# 1ch_motor_drive.net
KiCad netlist of a schematic drawn in Altium Designer
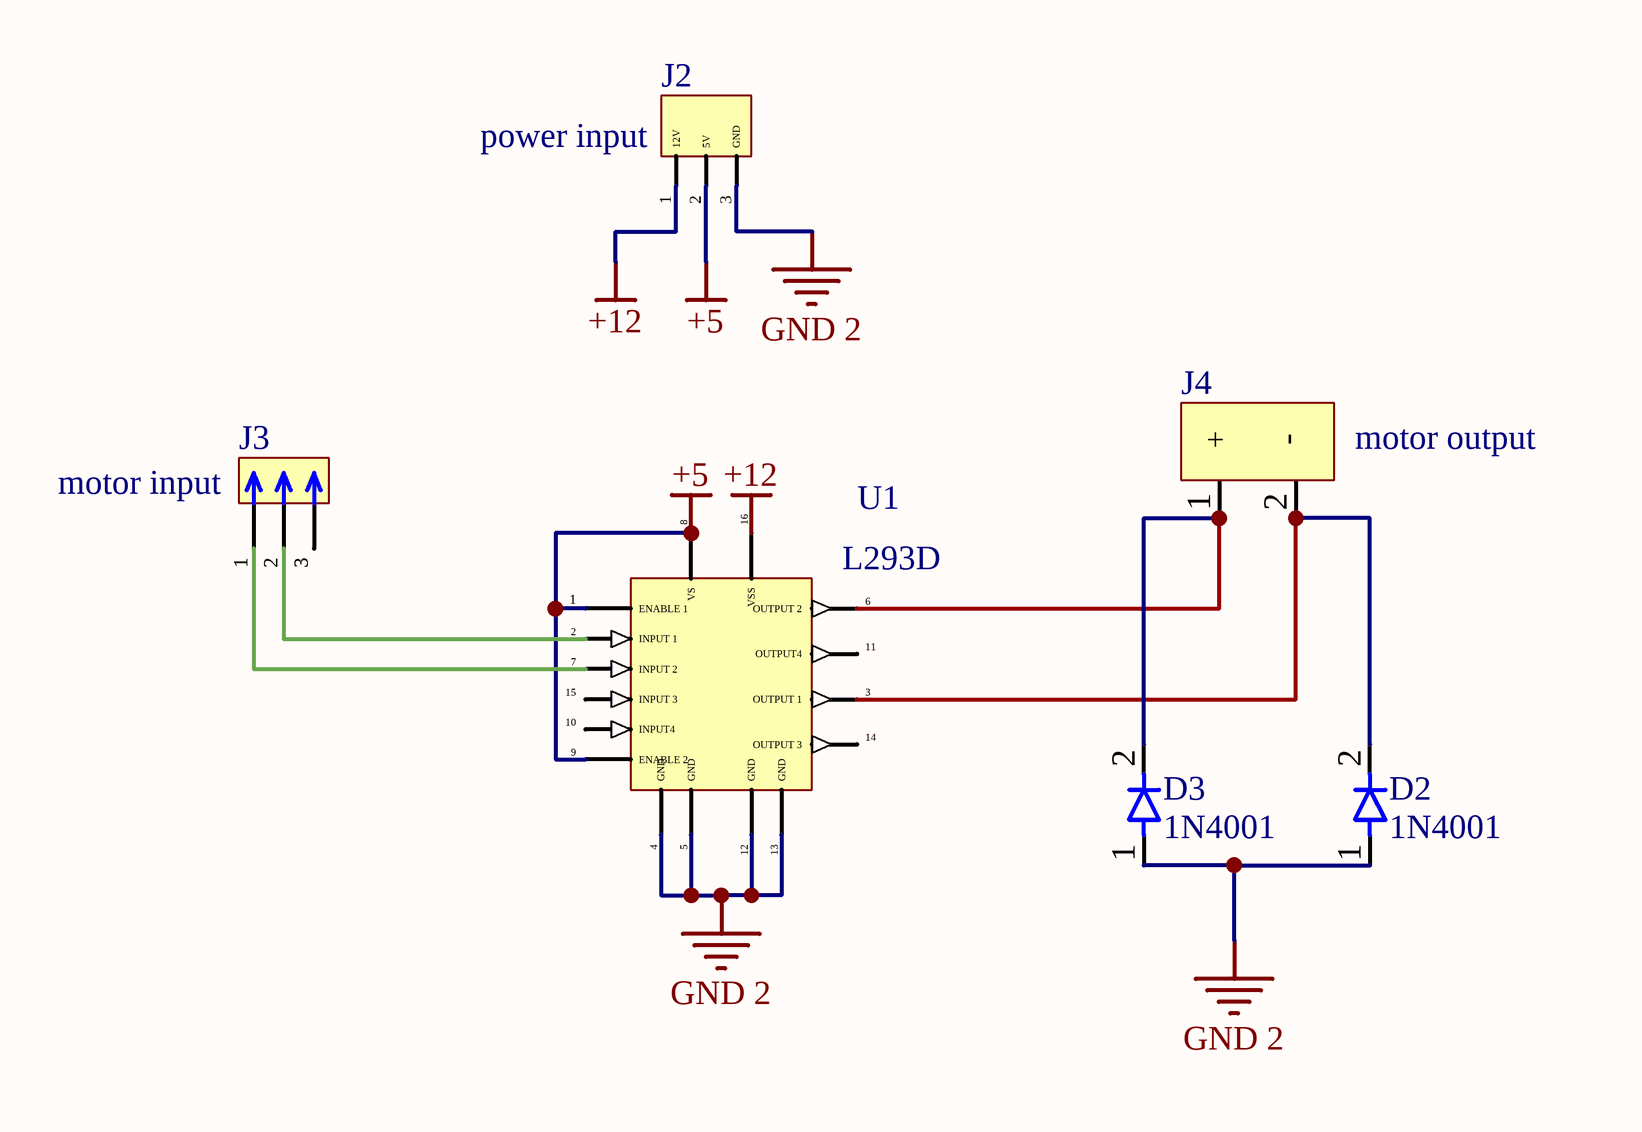
[diagram p0: 1ch motor drive.SchDoc]

(export (version "E")
  (design (tool "Eeschema 10.0.6"))
  (components
    (comp (ref "D2") (value "1N4001") (footprint "330ohm_TH") (libsource (lib "circuit19") (part "diode")))
    (comp (ref "D3") (value "1N4001") (footprint "330ohm_TH") (libsource (lib "circuit19") (part "diode")))
    (comp (ref "J2")
      (value "power input")
      (footprint "TERMINAL BLOCK 3PIN")
      (libsource (lib "circuit19") (part "3pin terminal block"))
    )
    (comp (ref "J3")
      (value "motor input")
      (footprint "pin header male")
      (libsource (lib "circuit19") (part "pin header male"))
    )
    (comp (ref "J4")
      (value "motor output")
      (footprint "header")
      (libsource (lib "circuit19") (part "terminal block_TH"))
    )
    (comp (ref "U1") (value "L293D") (footprint "L293D") (libsource (lib "circuit19") (part "L293d")))
  )
  (nets
    (net (code "1") (name "+5") (class "Default")
      (node (ref "J2") (pin "2") (pinfunction "5V_2") (pintype "passive"))
      (node (ref "U1") (pin "1") (pinfunction "ENABLE_1_1") (pintype "power_in"))
      (node (ref "U1") (pin "8") (pinfunction "VS_8") (pintype "power_in"))
      (node (ref "U1") (pin "9") (pinfunction "ENABLE_2_9") (pintype "power_in"))
    )
    (net (code "2") (name "+12") (class "Default")
      (node (ref "J2") (pin "1") (pinfunction "12V_1") (pintype "passive"))
      (node (ref "U1") (pin "16") (pinfunction "VSS_16") (pintype "power_in"))
    )
    (net (code "3") (name "GND 2") (class "Default")
      (node (ref "D2") (pin "1") (pinfunction "1_1") (pintype "passive"))
      (node (ref "D3") (pin "1") (pinfunction "1_1") (pintype "passive"))
      (node (ref "J2") (pin "3") (pinfunction "GND_3") (pintype "passive"))
      (node (ref "U1") (pin "12") (pinfunction "GND_12") (pintype "passive"))
      (node (ref "U1") (pin "13") (pinfunction "GND_13") (pintype "passive"))
      (node (ref "U1") (pin "4") (pinfunction "GND_4") (pintype "passive"))
      (node (ref "U1") (pin "5") (pinfunction "GND_5") (pintype "passive"))
    )
    (net (code "4") (name "Net-(U1-INPUT_1)") (class "Default")
      (node (ref "J3") (pin "2") (pintype "passive"))
      (node (ref "U1") (pin "2") (pinfunction "INPUT_1_2") (pintype "input"))
    )
    (net (code "5") (name "Net-(U1-INPUT_2)") (class "Default")
      (node (ref "J3") (pin "1") (pintype "passive"))
      (node (ref "U1") (pin "7") (pinfunction "INPUT_2_7") (pintype "input"))
    )
    (net (code "6") (name "Net-(U1-OUTPUT_1)") (class "Default")
      (node (ref "D2") (pin "2") (pinfunction "2_2") (pintype "passive"))
      (node (ref "J4") (pin "2") (pintype "passive"))
      (node (ref "U1") (pin "3") (pinfunction "OUTPUT_1_3") (pintype "output"))
    )
    (net (code "7") (name "Net-(U1-OUTPUT_2)") (class "Default")
      (node (ref "D3") (pin "2") (pinfunction "2_2") (pintype "passive"))
      (node (ref "J4") (pin "1") (pintype "passive"))
      (node (ref "U1") (pin "6") (pinfunction "OUTPUT_2_6") (pintype "output"))
    )
    (net (code "8") (name "unconnected-(J3-Pad3)") (class "Default")
      (node (ref "J3") (pin "3") (pintype "passive"))
    )
    (net (code "9") (name "unconnected-(U1-INPUT4-Pad10)") (class "Default")
      (node (ref "U1") (pin "10") (pinfunction "INPUT4_10") (pintype "input"))
    )
    (net (code "10") (name "unconnected-(U1-INPUT_3-Pad15)") (class "Default")
      (node (ref "U1") (pin "15") (pinfunction "INPUT_3_15") (pintype "input"))
    )
    (net (code "11") (name "unconnected-(U1-OUTPUT4-Pad11)") (class "Default")
      (node (ref "U1") (pin "11") (pinfunction "OUTPUT4_11") (pintype "output"))
    )
    (net (code "12") (name "unconnected-(U1-OUTPUT_3-Pad14)") (class "Default")
      (node (ref "U1") (pin "14") (pinfunction "OUTPUT_3_14") (pintype "output"))
    )
  )
)
